# RS485_UART_Multiplexer.net
KiCad netlist of a schematic drawn in Altium Designer
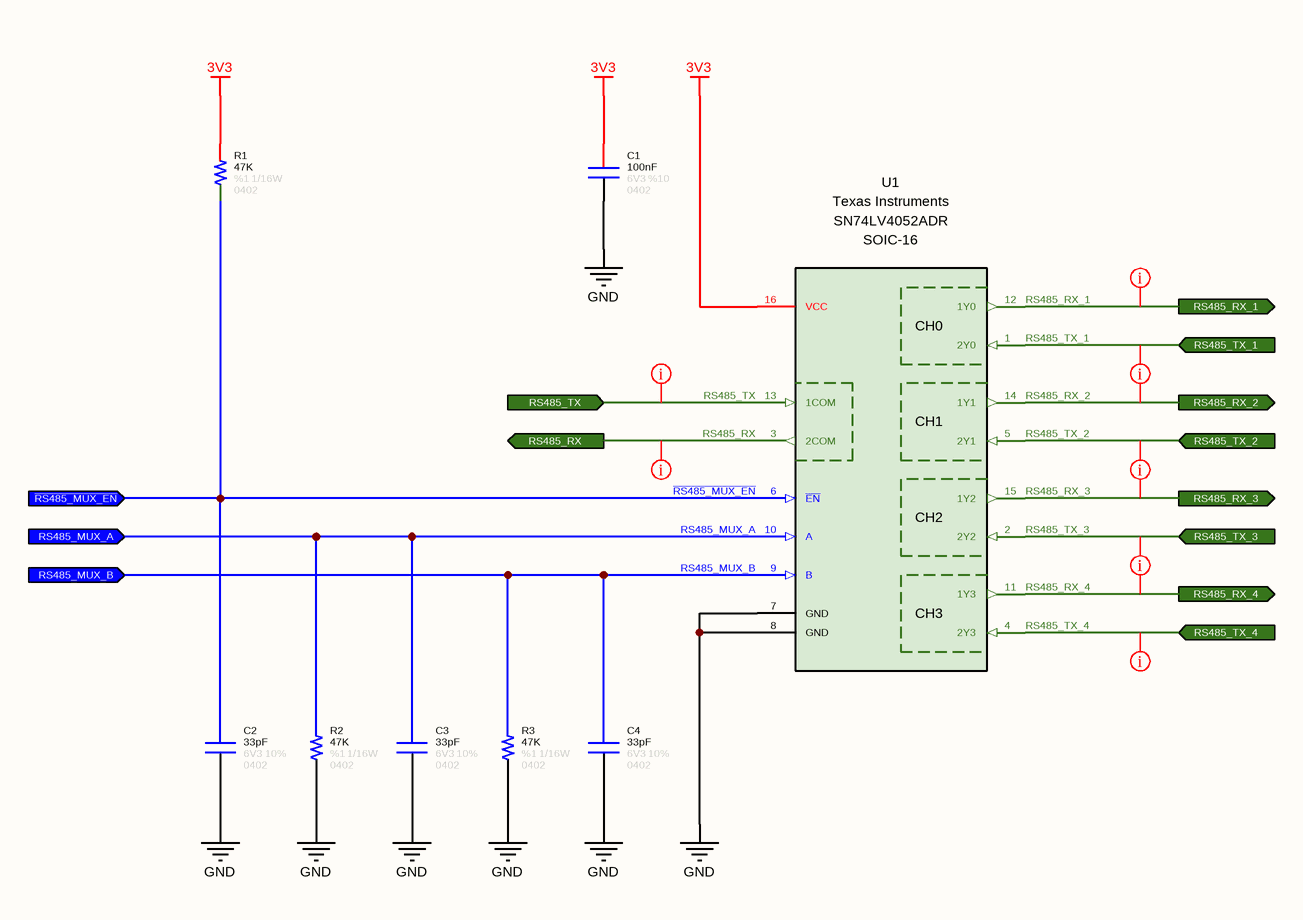
[diagram p0: RS485 UART Multiplexer.SchDoc]

(export (version "E")
  (design (tool "Eeschema 10.0.6"))
  (components
    (comp (ref "C1")
      (value "100nF")
      (footprint "CAPACITOR_0402")
      (description "Capacitor - 100nF [0402-6V3] (Ceramic)")
      (fields
        (field (name "MANUFACTURER PART NUMBER") "04026D104KAT4A")
        (field (name "TOLERANCE") "%10")
        (field (name "VOLTAGE") "6V3")
        (field (name "CASE") "0402")
        (field (name "Comment") "Capacitor - 100nF [0402] (Ceramic)")
      )
      (libsource (lib "Akkoyun") (part "Capacitor - 100nF [0402-6V3]"))
    )
    (comp (ref "C2")
      (value "33pF")
      (footprint "CAPACITOR_0402")
      (description "Capacitor - 33pF [0402] (Ceramic)")
      (fields
        (field (name "MANUFACTURER PART NUMBER") "C0402C330J9RACAUTO")
        (field (name "TOLERANCE") "10%")
        (field (name "CASE") "0402")
        (field (name "VOLTAGE") "6V3")
      )
      (libsource (lib "Akkoyun") (part "Capacitor - 33pF [0402-6V3]"))
    )
    (comp (ref "C3")
      (value "33pF")
      (footprint "CAPACITOR_0402")
      (description "Capacitor - 33pF [0402] (Ceramic)")
      (fields
        (field (name "MANUFACTURER PART NUMBER") "C0402C330J9RACAUTO")
        (field (name "TOLERANCE") "10%")
        (field (name "CASE") "0402")
        (field (name "VOLTAGE") "6V3")
      )
      (libsource (lib "Akkoyun") (part "Capacitor - 33pF [0402-6V3]"))
    )
    (comp (ref "C4")
      (value "33pF")
      (footprint "CAPACITOR_0402")
      (description "Capacitor - 33pF [0402] (Ceramic)")
      (fields
        (field (name "MANUFACTURER PART NUMBER") "C0402C330J9RACAUTO")
        (field (name "TOLERANCE") "10%")
        (field (name "CASE") "0402")
        (field (name "VOLTAGE") "6V3")
      )
      (libsource (lib "Akkoyun") (part "Capacitor - 33pF [0402-6V3]"))
    )
    (comp (ref "R1")
      (value "47K")
      (footprint "RESISTOR_0402")
      (description "Thick Film Resistors - SMD 1/16 W 47 KOhm 1%")
      (fields
        (field (name "MANUFACTURER PART NUMBER") "CRCW040247K0FKED")
        (field (name "TOLERANCE") "%1")
        (field (name "CASE") "0402")
        (field (name "POWER") "1/16W")
        (field (name "Comment") "47K - 0402 - %1 - 1/16W")
      )
      (libsource (lib "Akkoyun") (part "Resistor - 47K [0402]"))
    )
    (comp (ref "R2")
      (value "47K")
      (footprint "RESISTOR_0402")
      (description "Thick Film Resistors - SMD 1/16 W 47 KOhm 1%")
      (fields
        (field (name "MANUFACTURER PART NUMBER") "CRCW040247K0FKED")
        (field (name "TOLERANCE") "%1")
        (field (name "CASE") "0402")
        (field (name "POWER") "1/16W")
        (field (name "Comment") "47K - 0402 - %1 - 1/16W")
      )
      (libsource (lib "Akkoyun") (part "Resistor - 47K [0402]"))
    )
    (comp (ref "R3")
      (value "47K")
      (footprint "RESISTOR_0402")
      (description "Thick Film Resistors - SMD 1/16 W 47 KOhm 1%")
      (fields
        (field (name "MANUFACTURER PART NUMBER") "CRCW040247K0FKED")
        (field (name "TOLERANCE") "%1")
        (field (name "CASE") "0402")
        (field (name "POWER") "1/16W")
        (field (name "Comment") "47K - 0402 - %1 - 1/16W")
      )
      (libsource (lib "Akkoyun") (part "Resistor - 47K [0402]"))
    )
    (comp (ref "U1")
      (value "SN74LV4052ADR")
      (footprint "SOIC-16 Narrow")
      (description "Multiplexer Switch ICs Dual 4-Ch Analog Mltplxr/Demltplxr")
      (fields
        (field (name "MANUFACTURER NAME") "Texas Instruments")
        (field (name "MANUFACTURER PART NUMBER") "SN74LV4052ADR")
        (field (name "CASE") "SOIC-16")
      )
      (libsource (lib "Akkoyun") (part "IC - SN74LV4052ADR"))
    )
  )
  (nets
    (net (code "1") (name "/RS485_MUX_A") (class "Default")
      (node (ref "C3") (pin "2") (pinfunction "2_2") (pintype "passive"))
      (node (ref "R2") (pin "2") (pinfunction "2_2") (pintype "passive"))
      (node (ref "U1") (pin "10") (pinfunction "A_10") (pintype "input"))
    )
    (net (code "2") (name "/RS485_MUX_B") (class "Default")
      (node (ref "C4") (pin "2") (pinfunction "2_2") (pintype "passive"))
      (node (ref "R3") (pin "2") (pinfunction "2_2") (pintype "passive"))
      (node (ref "U1") (pin "9") (pinfunction "B_9") (pintype "input"))
    )
    (net (code "3") (name "/RS485_RX") (class "Default")
      (node (ref "U1") (pin "3") (pinfunction "2COM_3") (pintype "output"))
    )
    (net (code "4") (name "/RS485_RX_1") (class "Default")
      (node (ref "U1") (pin "12") (pinfunction "1Y0_12") (pintype "output"))
    )
    (net (code "5") (name "/RS485_RX_2") (class "Default")
      (node (ref "U1") (pin "14") (pinfunction "1Y1_14") (pintype "output"))
    )
    (net (code "6") (name "/RS485_RX_3") (class "Default")
      (node (ref "U1") (pin "15") (pinfunction "1Y2_15") (pintype "output"))
    )
    (net (code "7") (name "/RS485_RX_4") (class "Default")
      (node (ref "U1") (pin "11") (pinfunction "1Y3_11") (pintype "output"))
    )
    (net (code "8") (name "/RS485_TX") (class "Default")
      (node (ref "U1") (pin "13") (pinfunction "1COM_13") (pintype "input"))
    )
    (net (code "9") (name "/RS485_TX_1") (class "Default")
      (node (ref "U1") (pin "1") (pinfunction "2Y0_1") (pintype "input"))
    )
    (net (code "10") (name "/RS485_TX_2") (class "Default")
      (node (ref "U1") (pin "5") (pinfunction "2Y1_5") (pintype "input"))
    )
    (net (code "11") (name "/RS485_TX_3") (class "Default")
      (node (ref "U1") (pin "2") (pinfunction "2Y2_2") (pintype "input"))
    )
    (net (code "12") (name "/RS485_TX_4") (class "Default")
      (node (ref "U1") (pin "4") (pinfunction "2Y3_4") (pintype "input"))
    )
    (net (code "13") (name "/~{RS485_MUX_EN}") (class "Default")
      (node (ref "C2") (pin "2") (pinfunction "2_2") (pintype "passive"))
      (node (ref "R1") (pin "1") (pinfunction "1_1") (pintype "passive"))
      (node (ref "U1") (pin "6") (pinfunction "~{EN}_6") (pintype "input"))
    )
    (net (code "14") (name "3V3") (class "Default")
      (node (ref "C1") (pin "2") (pinfunction "2_2") (pintype "passive"))
      (node (ref "R1") (pin "2") (pinfunction "2_2") (pintype "passive"))
      (node (ref "U1") (pin "16") (pinfunction "VCC_16") (pintype "power_in"))
    )
    (net (code "15") (name "GND") (class "Default")
      (node (ref "C1") (pin "1") (pinfunction "1_1") (pintype "passive"))
      (node (ref "C2") (pin "1") (pinfunction "1_1") (pintype "passive"))
      (node (ref "C3") (pin "1") (pinfunction "1_1") (pintype "passive"))
      (node (ref "C4") (pin "1") (pinfunction "1_1") (pintype "passive"))
      (node (ref "R2") (pin "1") (pinfunction "1_1") (pintype "passive"))
      (node (ref "R3") (pin "1") (pinfunction "1_1") (pintype "passive"))
      (node (ref "U1") (pin "7") (pinfunction "GND_7") (pintype "power_in"))
      (node (ref "U1") (pin "8") (pinfunction "GND_8") (pintype "power_in"))
    )
  )
)
